# Motor_Slave___IMU_sensor.net
KiCad netlist of a schematic drawn in EAGLE
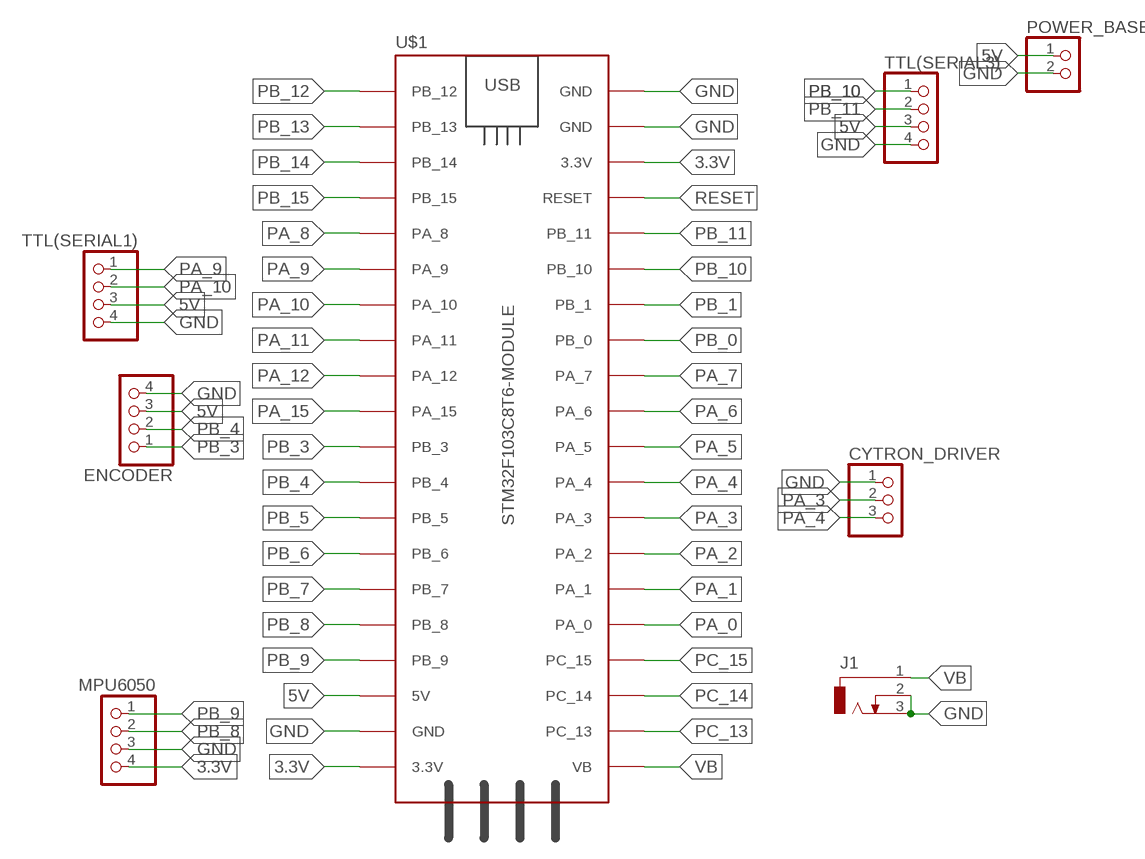
[diagram p0: schematic, sheet 1]

(export (version "E")
  (design (tool "Eeschema 10.0.6"))
  (components
    (comp (ref "CYTRON_DRIVER")
      (value "PINHD-3_DATA")
      (footprint "eagle-import:1X03_DATA")
      (libsource (lib "eagle-import") (part "PINHD-3_DATA"))
    )
    (comp (ref "ENCODER")
      (value "PINHD-4_DATA")
      (footprint "eagle-import:1X04_DATA")
      (libsource (lib "eagle-import") (part "PINHD-4_DATA"))
    )
    (comp (ref "J1")
      (value "CON_JACK")
      (footprint "eagle-import:DCJ0303")
      (libsource (lib "eagle-import") (part "CON_JACK"))
    )
    (comp (ref "MPU6050")
      (value "PINHD-4_DATA")
      (footprint "eagle-import:1X04_DATA")
      (libsource (lib "eagle-import") (part "PINHD-4_DATA"))
    )
    (comp (ref "POWER_BASE")
      (value "PINHD-2_DATA")
      (footprint "eagle-import:1X02_DATA")
      (libsource (lib "eagle-import") (part "PINHD-2_DATA"))
    )
    (comp (ref "TTL(SERIAL1)")
      (value "PINHD-4_DATA")
      (footprint "eagle-import:1X04_DATA")
      (libsource (lib "eagle-import") (part "PINHD-4_DATA"))
    )
    (comp (ref "TTL(SERIAL3)")
      (value "PINHD-4_DATA")
      (footprint "eagle-import:1X04_DATA")
      (libsource (lib "eagle-import") (part "PINHD-4_DATA"))
    )
    (comp (ref "U$1")
      (value "STM32F103C8T6-MODULE")
      (footprint "eagle-import:STM32F103C8T6-MODULE")
      (libsource (lib "eagle-import") (part "STM32F103C8T6-MODULE"))
    )
  )
  (nets
    (net (code "1") (name "3.3V") (class "Default")
      (node (ref "MPU6050") (pin "4") (pinfunction "4_4") (pintype "passive"))
      (node (ref "U$1") (pin "3.3V_1") (pinfunction "3.3V_3.3V_1") (pintype "bidirectional"))
      (node (ref "U$1") (pin "3.3V_2") (pinfunction "3.3V_3.3V_2") (pintype "bidirectional"))
    )
    (net (code "2") (name "5V") (class "Default")
      (node (ref "ENCODER") (pin "3") (pinfunction "3_3") (pintype "passive"))
      (node (ref "POWER_BASE") (pin "1") (pinfunction "1_1") (pintype "passive"))
      (node (ref "TTL(SERIAL1)") (pin "3") (pinfunction "3_3") (pintype "passive"))
      (node (ref "TTL(SERIAL3)") (pin "3") (pinfunction "3_3") (pintype "passive"))
      (node (ref "U$1") (pin "5V") (pinfunction "5V_5V") (pintype "bidirectional"))
    )
    (net (code "3") (name "GND") (class "Default")
      (node (ref "CYTRON_DRIVER") (pin "1") (pinfunction "1_1") (pintype "passive"))
      (node (ref "ENCODER") (pin "4") (pinfunction "4_4") (pintype "passive"))
      (node (ref "J1") (pin "2") (pinfunction "2_2") (pintype "passive"))
      (node (ref "J1") (pin "3") (pinfunction "3_3") (pintype "passive"))
      (node (ref "MPU6050") (pin "3") (pinfunction "3_3") (pintype "passive"))
      (node (ref "POWER_BASE") (pin "2") (pinfunction "2_2") (pintype "passive"))
      (node (ref "TTL(SERIAL1)") (pin "4") (pinfunction "4_4") (pintype "passive"))
      (node (ref "TTL(SERIAL3)") (pin "4") (pinfunction "4_4") (pintype "passive"))
      (node (ref "U$1") (pin "GND_1") (pinfunction "GND_GND_1") (pintype "bidirectional"))
      (node (ref "U$1") (pin "GND_2") (pinfunction "GND_GND_2") (pintype "bidirectional"))
      (node (ref "U$1") (pin "GND_3") (pinfunction "GND_GND_3") (pintype "power_in"))
    )
    (net (code "4") (name "PA_0") (class "Default")
      (node (ref "U$1") (pin "PA_0") (pinfunction "PA_0_PA_0") (pintype "bidirectional"))
    )
    (net (code "5") (name "PA_1") (class "Default")
      (node (ref "U$1") (pin "PA_1") (pinfunction "PA_1_PA_1") (pintype "bidirectional"))
    )
    (net (code "6") (name "PA_2") (class "Default")
      (node (ref "U$1") (pin "PA_2") (pinfunction "PA_2_PA_2") (pintype "bidirectional"))
    )
    (net (code "7") (name "PA_3") (class "Default")
      (node (ref "CYTRON_DRIVER") (pin "2") (pinfunction "2_2") (pintype "passive"))
      (node (ref "U$1") (pin "PA_3") (pinfunction "PA_3_PA_3") (pintype "bidirectional"))
    )
    (net (code "8") (name "PA_4") (class "Default")
      (node (ref "CYTRON_DRIVER") (pin "3") (pinfunction "3_3") (pintype "passive"))
      (node (ref "U$1") (pin "PA_4") (pinfunction "PA_4_PA_4") (pintype "bidirectional"))
    )
    (net (code "9") (name "PA_5") (class "Default")
      (node (ref "U$1") (pin "PA_5") (pinfunction "PA_5_PA_5") (pintype "bidirectional"))
    )
    (net (code "10") (name "PA_6") (class "Default")
      (node (ref "U$1") (pin "PA_6") (pinfunction "PA_6_PA_6") (pintype "bidirectional"))
    )
    (net (code "11") (name "PA_7") (class "Default")
      (node (ref "U$1") (pin "PA_7") (pinfunction "PA_7_PA_7") (pintype "bidirectional"))
    )
    (net (code "12") (name "PA_8") (class "Default")
      (node (ref "U$1") (pin "PA_8") (pinfunction "PA_8_PA_8") (pintype "bidirectional"))
    )
    (net (code "13") (name "PA_9") (class "Default")
      (node (ref "TTL(SERIAL1)") (pin "1") (pinfunction "1_1") (pintype "passive"))
      (node (ref "U$1") (pin "PA_9") (pinfunction "PA_9_PA_9") (pintype "bidirectional"))
    )
    (net (code "14") (name "PA_10") (class "Default")
      (node (ref "TTL(SERIAL1)") (pin "2") (pinfunction "2_2") (pintype "passive"))
      (node (ref "U$1") (pin "PA_10") (pinfunction "PA_10_PA_10") (pintype "bidirectional"))
    )
    (net (code "15") (name "PA_11") (class "Default")
      (node (ref "U$1") (pin "PA_11") (pinfunction "PA_11_PA_11") (pintype "bidirectional"))
    )
    (net (code "16") (name "PA_12") (class "Default")
      (node (ref "U$1") (pin "PA_12") (pinfunction "PA_12_PA_12") (pintype "bidirectional"))
    )
    (net (code "17") (name "PA_15") (class "Default")
      (node (ref "U$1") (pin "PA_15") (pinfunction "PA_15_PA_15") (pintype "bidirectional"))
    )
    (net (code "18") (name "PB_0") (class "Default")
      (node (ref "U$1") (pin "PB_0") (pinfunction "PB_0_PB_0") (pintype "bidirectional"))
    )
    (net (code "19") (name "PB_1") (class "Default")
      (node (ref "U$1") (pin "PB_1") (pinfunction "PB_1_PB_1") (pintype "bidirectional"))
    )
    (net (code "20") (name "PB_3") (class "Default")
      (node (ref "ENCODER") (pin "1") (pinfunction "1_1") (pintype "passive"))
      (node (ref "U$1") (pin "PB_3") (pinfunction "PB_3_PB_3") (pintype "bidirectional"))
    )
    (net (code "21") (name "PB_4") (class "Default")
      (node (ref "ENCODER") (pin "2") (pinfunction "2_2") (pintype "passive"))
      (node (ref "U$1") (pin "PB_4") (pinfunction "PB_4_PB_4") (pintype "bidirectional"))
    )
    (net (code "22") (name "PB_5") (class "Default")
      (node (ref "U$1") (pin "PB_5") (pinfunction "PB_5_PB_5") (pintype "bidirectional"))
    )
    (net (code "23") (name "PB_6") (class "Default")
      (node (ref "U$1") (pin "PB_6") (pinfunction "PB_6_PB_6") (pintype "bidirectional"))
    )
    (net (code "24") (name "PB_7") (class "Default")
      (node (ref "U$1") (pin "PB_7") (pinfunction "PB_7_PB_7") (pintype "bidirectional"))
    )
    (net (code "25") (name "PB_8") (class "Default")
      (node (ref "MPU6050") (pin "2") (pinfunction "2_2") (pintype "passive"))
      (node (ref "U$1") (pin "PB_8") (pinfunction "PB_8_PB_8") (pintype "bidirectional"))
    )
    (net (code "26") (name "PB_9") (class "Default")
      (node (ref "MPU6050") (pin "1") (pinfunction "1_1") (pintype "passive"))
      (node (ref "U$1") (pin "PB_9") (pinfunction "PB_9_PB_9") (pintype "bidirectional"))
    )
    (net (code "27") (name "PB_10") (class "Default")
      (node (ref "TTL(SERIAL3)") (pin "1") (pinfunction "1_1") (pintype "passive"))
      (node (ref "U$1") (pin "PB_10") (pinfunction "PB_10_PB_10") (pintype "bidirectional"))
    )
    (net (code "28") (name "PB_11") (class "Default")
      (node (ref "TTL(SERIAL3)") (pin "2") (pinfunction "2_2") (pintype "passive"))
      (node (ref "U$1") (pin "PB_11") (pinfunction "PB_11_PB_11") (pintype "bidirectional"))
    )
    (net (code "29") (name "PB_12") (class "Default")
      (node (ref "U$1") (pin "PB_12") (pinfunction "PB_12_PB_12") (pintype "bidirectional"))
    )
    (net (code "30") (name "PB_13") (class "Default")
      (node (ref "U$1") (pin "PB_13") (pinfunction "PB_13_PB_13") (pintype "bidirectional"))
    )
    (net (code "31") (name "PB_14") (class "Default")
      (node (ref "U$1") (pin "PB_14") (pinfunction "PB_14_PB_14") (pintype "bidirectional"))
    )
    (net (code "32") (name "PB_15") (class "Default")
      (node (ref "U$1") (pin "PB_15") (pinfunction "PB_15_PB_15") (pintype "bidirectional"))
    )
    (net (code "33") (name "PC_13") (class "Default")
      (node (ref "U$1") (pin "PC_13") (pinfunction "PC_13_PC_13") (pintype "bidirectional"))
    )
    (net (code "34") (name "PC_14") (class "Default")
      (node (ref "U$1") (pin "PC_14") (pinfunction "PC_14_PC_14") (pintype "bidirectional"))
    )
    (net (code "35") (name "PC_15") (class "Default")
      (node (ref "U$1") (pin "PC_15") (pinfunction "PC_15_PC_15") (pintype "bidirectional"))
    )
    (net (code "36") (name "RESET") (class "Default")
      (node (ref "U$1") (pin "RESET") (pinfunction "RESET_RESET") (pintype "bidirectional"))
    )
    (net (code "37") (name "VB") (class "Default")
      (node (ref "J1") (pin "1") (pinfunction "1_1") (pintype "passive"))
      (node (ref "U$1") (pin "VB") (pinfunction "VB_VB") (pintype "bidirectional"))
    )
  )
)
